# Sheet1.net
KiCad netlist of a schematic drawn in Altium Designer
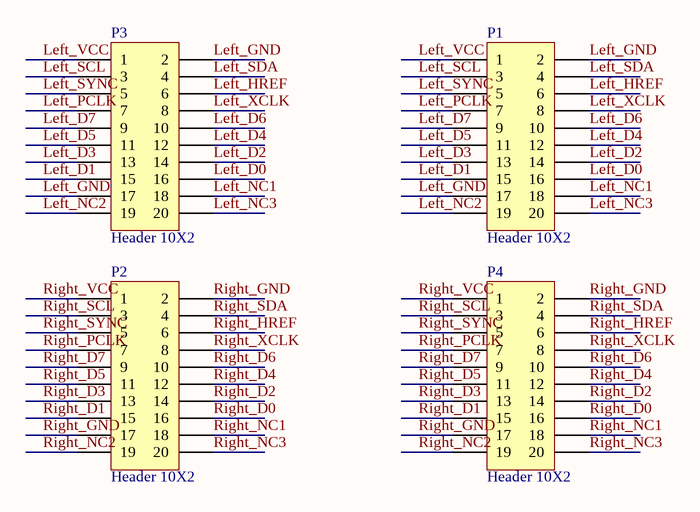
[diagram p0: Sheet1.SchDoc]

(export (version "E")
  (design (tool "Eeschema 10.0.6"))
  (components
    (comp (ref "P1")
      (value "Header 10X2")
      (footprint "HDR2X10")
      (description "Header, 10-Pin, Dual row")
      (fields (field (name "PUBLISHER") "Altium Limited"))
      (libsource (lib "Miscellaneous Connectors") (part "Header 10X2"))
    )
    (comp (ref "P2")
      (value "Header 10X2")
      (footprint "HDR2X10")
      (description "Header, 10-Pin, Dual row")
      (fields (field (name "PUBLISHER") "Altium Limited"))
      (libsource (lib "Miscellaneous Connectors") (part "Header 10X2"))
    )
    (comp (ref "P3")
      (value "Header 10X2")
      (footprint "HDR2X10")
      (description "Header, 10-Pin, Dual row")
      (fields (field (name "PUBLISHER") "Altium Limited"))
      (libsource (lib "Miscellaneous Connectors") (part "Header 10X2"))
    )
    (comp (ref "P4")
      (value "Header 10X2")
      (footprint "HDR2X10")
      (description "Header, 10-Pin, Dual row")
      (fields (field (name "PUBLISHER") "Altium Limited"))
      (libsource (lib "Miscellaneous Connectors") (part "Header 10X2"))
    )
  )
  (nets
    (net (code "1") (name "/Left_D0") (class "Default")
      (node (ref "P1") (pin "16") (pinfunction "16_16") (pintype "passive"))
      (node (ref "P3") (pin "16") (pinfunction "16_16") (pintype "passive"))
    )
    (net (code "2") (name "/Left_D1") (class "Default")
      (node (ref "P1") (pin "15") (pinfunction "15_15") (pintype "passive"))
      (node (ref "P3") (pin "15") (pinfunction "15_15") (pintype "passive"))
    )
    (net (code "3") (name "/Left_D2") (class "Default")
      (node (ref "P1") (pin "14") (pinfunction "14_14") (pintype "passive"))
      (node (ref "P3") (pin "14") (pinfunction "14_14") (pintype "passive"))
    )
    (net (code "4") (name "/Left_D3") (class "Default")
      (node (ref "P1") (pin "13") (pinfunction "13_13") (pintype "passive"))
      (node (ref "P3") (pin "13") (pinfunction "13_13") (pintype "passive"))
    )
    (net (code "5") (name "/Left_D4") (class "Default")
      (node (ref "P1") (pin "12") (pinfunction "12_12") (pintype "passive"))
      (node (ref "P3") (pin "12") (pinfunction "12_12") (pintype "passive"))
    )
    (net (code "6") (name "/Left_D5") (class "Default")
      (node (ref "P1") (pin "11") (pinfunction "11_11") (pintype "passive"))
      (node (ref "P3") (pin "11") (pinfunction "11_11") (pintype "passive"))
    )
    (net (code "7") (name "/Left_D6") (class "Default")
      (node (ref "P1") (pin "10") (pinfunction "10_10") (pintype "passive"))
      (node (ref "P3") (pin "10") (pinfunction "10_10") (pintype "passive"))
    )
    (net (code "8") (name "/Left_D7") (class "Default")
      (node (ref "P1") (pin "9") (pinfunction "9_9") (pintype "passive"))
      (node (ref "P3") (pin "9") (pinfunction "9_9") (pintype "passive"))
    )
    (net (code "9") (name "/Left_GND") (class "Default")
      (node (ref "P1") (pin "17") (pinfunction "17_17") (pintype "passive"))
      (node (ref "P1") (pin "2") (pinfunction "2_2") (pintype "passive"))
      (node (ref "P3") (pin "17") (pinfunction "17_17") (pintype "passive"))
      (node (ref "P3") (pin "2") (pinfunction "2_2") (pintype "passive"))
    )
    (net (code "10") (name "/Left_HREF") (class "Default")
      (node (ref "P1") (pin "6") (pinfunction "6_6") (pintype "passive"))
      (node (ref "P3") (pin "6") (pinfunction "6_6") (pintype "passive"))
    )
    (net (code "11") (name "/Left_NC1") (class "Default")
      (node (ref "P1") (pin "18") (pinfunction "18_18") (pintype "passive"))
      (node (ref "P3") (pin "18") (pinfunction "18_18") (pintype "passive"))
    )
    (net (code "12") (name "/Left_NC2") (class "Default")
      (node (ref "P1") (pin "19") (pinfunction "19_19") (pintype "passive"))
      (node (ref "P3") (pin "19") (pinfunction "19_19") (pintype "passive"))
    )
    (net (code "13") (name "/Left_NC3") (class "Default")
      (node (ref "P1") (pin "20") (pinfunction "20_20") (pintype "passive"))
      (node (ref "P3") (pin "20") (pinfunction "20_20") (pintype "passive"))
    )
    (net (code "14") (name "/Left_PCLK") (class "Default")
      (node (ref "P1") (pin "7") (pinfunction "7_7") (pintype "passive"))
      (node (ref "P3") (pin "7") (pinfunction "7_7") (pintype "passive"))
    )
    (net (code "15") (name "/Left_SCL") (class "Default")
      (node (ref "P1") (pin "3") (pinfunction "3_3") (pintype "passive"))
      (node (ref "P3") (pin "3") (pinfunction "3_3") (pintype "passive"))
    )
    (net (code "16") (name "/Left_SDA") (class "Default")
      (node (ref "P1") (pin "4") (pinfunction "4_4") (pintype "passive"))
      (node (ref "P3") (pin "4") (pinfunction "4_4") (pintype "passive"))
    )
    (net (code "17") (name "/Left_SYNC") (class "Default")
      (node (ref "P1") (pin "5") (pinfunction "5_5") (pintype "passive"))
      (node (ref "P3") (pin "5") (pinfunction "5_5") (pintype "passive"))
    )
    (net (code "18") (name "/Left_VCC") (class "Default")
      (node (ref "P1") (pin "1") (pinfunction "1_1") (pintype "passive"))
      (node (ref "P3") (pin "1") (pinfunction "1_1") (pintype "passive"))
    )
    (net (code "19") (name "/Left_XCLK") (class "Default")
      (node (ref "P1") (pin "8") (pinfunction "8_8") (pintype "passive"))
      (node (ref "P3") (pin "8") (pinfunction "8_8") (pintype "passive"))
    )
    (net (code "20") (name "/Right_D0") (class "Default")
      (node (ref "P2") (pin "16") (pinfunction "16_16") (pintype "passive"))
      (node (ref "P4") (pin "16") (pinfunction "16_16") (pintype "passive"))
    )
    (net (code "21") (name "/Right_D1") (class "Default")
      (node (ref "P2") (pin "15") (pinfunction "15_15") (pintype "passive"))
      (node (ref "P4") (pin "15") (pinfunction "15_15") (pintype "passive"))
    )
    (net (code "22") (name "/Right_D2") (class "Default")
      (node (ref "P2") (pin "14") (pinfunction "14_14") (pintype "passive"))
      (node (ref "P4") (pin "14") (pinfunction "14_14") (pintype "passive"))
    )
    (net (code "23") (name "/Right_D3") (class "Default")
      (node (ref "P2") (pin "13") (pinfunction "13_13") (pintype "passive"))
      (node (ref "P4") (pin "13") (pinfunction "13_13") (pintype "passive"))
    )
    (net (code "24") (name "/Right_D4") (class "Default")
      (node (ref "P2") (pin "12") (pinfunction "12_12") (pintype "passive"))
      (node (ref "P4") (pin "12") (pinfunction "12_12") (pintype "passive"))
    )
    (net (code "25") (name "/Right_D5") (class "Default")
      (node (ref "P2") (pin "11") (pinfunction "11_11") (pintype "passive"))
      (node (ref "P4") (pin "11") (pinfunction "11_11") (pintype "passive"))
    )
    (net (code "26") (name "/Right_D6") (class "Default")
      (node (ref "P2") (pin "10") (pinfunction "10_10") (pintype "passive"))
      (node (ref "P4") (pin "10") (pinfunction "10_10") (pintype "passive"))
    )
    (net (code "27") (name "/Right_D7") (class "Default")
      (node (ref "P2") (pin "9") (pinfunction "9_9") (pintype "passive"))
      (node (ref "P4") (pin "9") (pinfunction "9_9") (pintype "passive"))
    )
    (net (code "28") (name "/Right_GND") (class "Default")
      (node (ref "P2") (pin "17") (pinfunction "17_17") (pintype "passive"))
      (node (ref "P2") (pin "2") (pinfunction "2_2") (pintype "passive"))
      (node (ref "P4") (pin "17") (pinfunction "17_17") (pintype "passive"))
      (node (ref "P4") (pin "2") (pinfunction "2_2") (pintype "passive"))
    )
    (net (code "29") (name "/Right_HREF") (class "Default")
      (node (ref "P2") (pin "6") (pinfunction "6_6") (pintype "passive"))
      (node (ref "P4") (pin "6") (pinfunction "6_6") (pintype "passive"))
    )
    (net (code "30") (name "/Right_NC1") (class "Default")
      (node (ref "P2") (pin "18") (pinfunction "18_18") (pintype "passive"))
      (node (ref "P4") (pin "18") (pinfunction "18_18") (pintype "passive"))
    )
    (net (code "31") (name "/Right_NC2") (class "Default")
      (node (ref "P2") (pin "19") (pinfunction "19_19") (pintype "passive"))
      (node (ref "P4") (pin "19") (pinfunction "19_19") (pintype "passive"))
    )
    (net (code "32") (name "/Right_NC3") (class "Default")
      (node (ref "P2") (pin "20") (pinfunction "20_20") (pintype "passive"))
      (node (ref "P4") (pin "20") (pinfunction "20_20") (pintype "passive"))
    )
    (net (code "33") (name "/Right_PCLK") (class "Default")
      (node (ref "P2") (pin "7") (pinfunction "7_7") (pintype "passive"))
      (node (ref "P4") (pin "7") (pinfunction "7_7") (pintype "passive"))
    )
    (net (code "34") (name "/Right_SCL") (class "Default")
      (node (ref "P2") (pin "3") (pinfunction "3_3") (pintype "passive"))
      (node (ref "P4") (pin "3") (pinfunction "3_3") (pintype "passive"))
    )
    (net (code "35") (name "/Right_SDA") (class "Default")
      (node (ref "P2") (pin "4") (pinfunction "4_4") (pintype "passive"))
      (node (ref "P4") (pin "4") (pinfunction "4_4") (pintype "passive"))
    )
    (net (code "36") (name "/Right_SYNC") (class "Default")
      (node (ref "P2") (pin "5") (pinfunction "5_5") (pintype "passive"))
      (node (ref "P4") (pin "5") (pinfunction "5_5") (pintype "passive"))
    )
    (net (code "37") (name "/Right_VCC") (class "Default")
      (node (ref "P2") (pin "1") (pinfunction "1_1") (pintype "passive"))
      (node (ref "P4") (pin "1") (pinfunction "1_1") (pintype "passive"))
    )
    (net (code "38") (name "/Right_XCLK") (class "Default")
      (node (ref "P2") (pin "8") (pinfunction "8_8") (pintype "passive"))
      (node (ref "P4") (pin "8") (pinfunction "8_8") (pintype "passive"))
    )
  )
)
